# mainboard_v1.net
KiCad netlist of a schematic drawn in Altium Designer
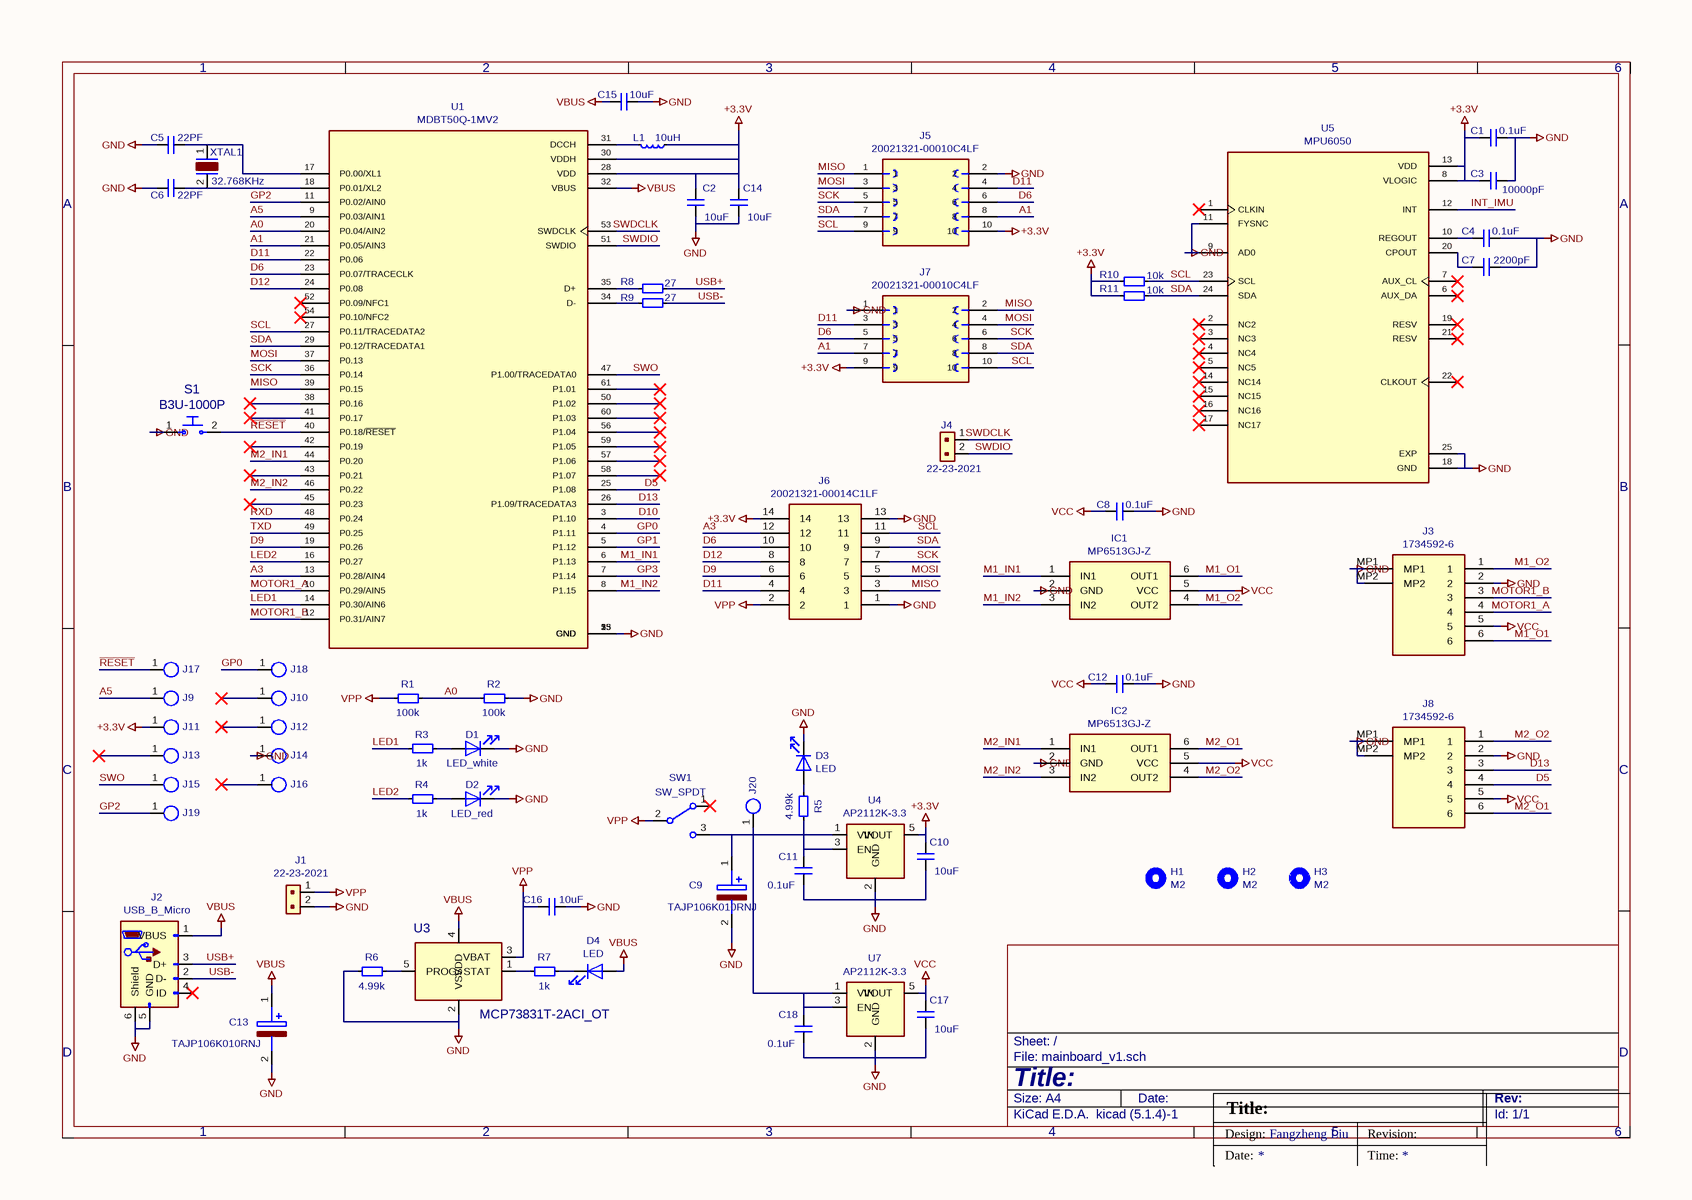
[diagram p0: mainboard_v1.SchDoc]

(export (version "E")
  (design (tool "Eeschema 10.0.6"))
  (components
    (comp (ref "C1") (value "0.1uF") (libsource (lib "Device") (part "C_Small")))
    (comp (ref "C2") (value "10uF") (libsource (lib "Device") (part "C_Small")))
    (comp (ref "C3") (value "10000pF") (libsource (lib "Device") (part "C_Small")))
    (comp (ref "C4") (value "0.1uF") (libsource (lib "Device") (part "C_Small")))
    (comp (ref "C5") (value "22PF") (libsource (lib "Device") (part "C_Small")))
    (comp (ref "C6") (value "22PF") (libsource (lib "Device") (part "C_Small")))
    (comp (ref "C7") (value "2200pF") (libsource (lib "Device") (part "C_Small")))
    (comp (ref "C8") (value "0.1uF") (libsource (lib "Device") (part "C_Small")))
    (comp (ref "C9")
      (value "TAJP106K010RNJ")
      (description "Tantalum Capacitors - Solid SMD 10V 10uF 10%")
      (fields (field (name "MOUSER PART NUMBER") "581-TAJP106K010RNJ"))
      (libsource (lib "SamacSys_Parts") (part "TAJP106K010RNJ"))
    )
    (comp (ref "C10") (value "10uF") (libsource (lib "Device") (part "C_Small")))
    (comp (ref "C11") (value "0.1uF") (libsource (lib "Device") (part "C_Small")))
    (comp (ref "C12") (value "0.1uF") (libsource (lib "Device") (part "C_Small")))
    (comp (ref "C13")
      (value "TAJP106K010RNJ")
      (description "Tantalum Capacitors - Solid SMD 10V 10uF 10%")
      (fields (field (name "MOUSER PART NUMBER") "581-TAJP106K010RNJ"))
      (libsource (lib "SamacSys_Parts") (part "TAJP106K010RNJ"))
    )
    (comp (ref "C14") (value "10uF") (libsource (lib "Device") (part "C_Small")))
    (comp (ref "C15") (value "10uF") (libsource (lib "Device") (part "C_Small")))
    (comp (ref "C16") (value "10uF") (libsource (lib "Device") (part "C_Small")))
    (comp (ref "C17") (value "10uF") (libsource (lib "Device") (part "C_Small")))
    (comp (ref "C18") (value "0.1uF") (libsource (lib "Device") (part "C_Small")))
    (comp (ref "D1") (value "LED_white") (libsource (lib "Device") (part "LED")))
    (comp (ref "D2") (value "LED_red") (libsource (lib "Device") (part "LED")))
    (comp (ref "D3") (value "LED") (libsource (lib "Device") (part "LED")))
    (comp (ref "D4") (value "LED") (libsource (lib "Device") (part "LED")))
    (comp (ref "H1") (value "M2") (libsource (lib "Mechanical") (part "MountingHole")))
    (comp (ref "H2") (value "M2") (libsource (lib "Mechanical") (part "MountingHole")))
    (comp (ref "H3") (value "M2") (libsource (lib "Mechanical") (part "MountingHole")))
    (comp (ref "IC1")
      (value "MP6513GJ-Z")
      (description "Power Switch ICs - Power Distribution 2.5V-21V 0.8A Half Bridge Motor Driver")
      (fields (field (name "MOUSER PART NUMBER") "946-MP6513GJ-Z"))
      (libsource (lib "SamacSys_Parts") (part "MP6513GJ-Z"))
    )
    (comp (ref "IC2")
      (value "MP6513GJ-Z")
      (description "Power Switch ICs - Power Distribution 2.5V-21V 0.8A Half Bridge Motor Driver")
      (fields (field (name "MOUSER PART NUMBER") "946-MP6513GJ-Z"))
      (libsource (lib "SamacSys_Parts") (part "MP6513GJ-Z"))
    )
    (comp (ref "J1")
      (value "22-23-2021")
      (description "CONN HEADER VERT 2POS 2.54MM")
      (fields (field (name "MANUFACTURER") "Molex"))
      (libsource (lib "dk_Rectangular-Connectors-Headers-Male-Pins") (part "22-23-2021"))
    )
    (comp (ref "J2") (value "USB_B_Micro") (libsource (lib "Connector") (part "USB_B_Micro")))
    (comp (ref "J3")
      (value "1734592-6")
      (description "FFC & FPC Connectors FPC CONN. 0.5MM PITCH B/C 6P")
      (fields (field (name "MOUSER PART NUMBER") "571-1734592-6"))
      (libsource (lib "SamacSys_Parts") (part "1734592-6"))
    )
    (comp (ref "J4")
      (value "22-23-2021")
      (description "CONN HEADER VERT 2POS 2.54MM")
      (fields (field (name "MANUFACTURER") "Molex"))
      (libsource (lib "dk_Rectangular-Connectors-Headers-Male-Pins") (part "22-23-2021"))
    )
    (comp (ref "J5")
      (value "20021321-00010C4LF")
      (fields (field (name "MANUFACTURER") "Harwin Inc."))
      (libsource (lib "M50-3100545") (part "M50-3100545"))
    )
    (comp (ref "J6")
      (value "20021321-00014C1LF")
      (description "Headers & Wire Housings 20021321-00014C1LF-RECEPTACLE VT SMT")
      (fields (field (name "MOUSER PART NUMBER") "649-20213210014C1LF"))
      (libsource (lib "SamacSys_Parts") (part "20021321-00014C1LF"))
    )
    (comp (ref "J7")
      (value "20021321-00010C4LF")
      (fields (field (name "MANUFACTURER") "Harwin Inc."))
      (libsource (lib "M50-3100545") (part "M50-3100545"))
    )
    (comp (ref "J8")
      (value "1734592-6")
      (description "FFC & FPC Connectors FPC CONN. 0.5MM PITCH B/C 6P")
      (fields (field (name "MOUSER PART NUMBER") "571-1734592-6"))
      (libsource (lib "SamacSys_Parts") (part "1734592-6"))
    )
    (comp (ref "J9") (value "1_pin_sig") (libsource (lib "Mylib") (part "1_pin_sig")))
    (comp (ref "J10") (value "1_pin_sig") (libsource (lib "Mylib") (part "1_pin_sig")))
    (comp (ref "J11") (value "1_pin_sig") (libsource (lib "Mylib") (part "1_pin_sig")))
    (comp (ref "J12") (value "1_pin_sig") (libsource (lib "Mylib") (part "1_pin_sig")))
    (comp (ref "J13") (value "1_pin_sig") (libsource (lib "Mylib") (part "1_pin_sig")))
    (comp (ref "J14") (value "1_pin_sig") (libsource (lib "Mylib") (part "1_pin_sig")))
    (comp (ref "J15") (value "1_pin_sig") (libsource (lib "Mylib") (part "1_pin_sig")))
    (comp (ref "J16") (value "1_pin_sig") (libsource (lib "Mylib") (part "1_pin_sig")))
    (comp (ref "J17") (value "1_pin_sig") (libsource (lib "Mylib") (part "1_pin_sig")))
    (comp (ref "J18") (value "1_pin_sig") (libsource (lib "Mylib") (part "1_pin_sig")))
    (comp (ref "J19") (value "1_pin_sig") (libsource (lib "Mylib") (part "1_pin_sig")))
    (comp (ref "J20") (value "1_pin_sig") (libsource (lib "Mylib") (part "1_pin_sig")))
    (comp (ref "L1") (value "10uH") (libsource (lib "Device") (part "L_Small")))
    (comp (ref "R1") (value "100k") (libsource (lib "Device") (part "R_Small")))
    (comp (ref "R2") (value "100k") (libsource (lib "Device") (part "R_Small")))
    (comp (ref "R3") (value "1k") (libsource (lib "Device") (part "R_Small")))
    (comp (ref "R4") (value "1k") (libsource (lib "Device") (part "R_Small")))
    (comp (ref "R5") (value "4.99k") (libsource (lib "") (part "R_Small_1")))
    (comp (ref "R6") (value "4.99k") (libsource (lib "Device") (part "R_Small")))
    (comp (ref "R7") (value "1k") (libsource (lib "Device") (part "R_Small")))
    (comp (ref "R8") (value "27") (libsource (lib "Device") (part "R_Small")))
    (comp (ref "R9") (value "27") (libsource (lib "Device") (part "R_Small")))
    (comp (ref "R10") (value "10k") (libsource (lib "Device") (part "R_Small")))
    (comp (ref "R11") (value "10k") (libsource (lib "Device") (part "R_Small")))
    (comp (ref "S1")
      (value "B3U-1000P")
      (description "SWITCH TACTILE SPST-NO 0.05A 12V")
      (fields (field (name "MANUFACTURER") "Omron Electronics Inc-EMC Div"))
      (libsource (lib "dk_Tactile-Switches") (part "B3U-1000P"))
    )
    (comp (ref "SW1") (value "SW_SPDT") (libsource (lib "Switch") (part "SW_SPDT")))
    (comp (ref "U1")
      (value "MDBT50Q-1MV2")
      (fields (field (name "MANUFACTURER") "RAYTAC"))
      (libsource (lib "MDBT50Q-1MV2") (part "MDBT50Q-1MV2"))
    )
    (comp (ref "U3")
      (value "MCP73831T-2ACI_OT")
      (description "IC CONTROLLR LI-ION 4.2V SOT23-5")
      (fields (field (name "MPN") "MCP73831T-2ACI/OT") (field (name "MANUFACTURER") "Microchip Technology"))
      (libsource (lib "dk_PMIC-Battery-Chargers") (part "MCP73831T-2ACI_OT"))
    )
    (comp (ref "U4") (value "AP2112K-3.3") (libsource (lib "Regulator_Linear") (part "AP2112K-3.3")))
    (comp (ref "U5")
      (value "MPU6050")
      (fields (field (name "MANUFACTURER") "TDK InvenSense"))
      (libsource (lib "MPU6050") (part "MPU6050"))
    )
    (comp (ref "U7") (value "AP2112K-3.3") (libsource (lib "Regulator_Linear") (part "AP2112K-3.3")))
    (comp (ref "XTAL1")
      (value "32.768KHz")
      (description "CRYSTAL 32.7680KHZ 12.5PF SMD")
      (fields (field (name "MPN") "ECS-.327-12.5-34B-TR") (field (name "MANUFACTURER") "ECS Inc."))
      (libsource (lib "dk_Crystals") (part "ECS-_327-12_5-34B-TR"))
    )
  )
  (nets
    (net (code "1") (name "+3.3V") (class "Default")
      (node (ref "C1") (pin "2") (pinfunction "2_2") (pintype "passive"))
      (node (ref "C10") (pin "2") (pinfunction "2_2") (pintype "passive"))
      (node (ref "C14") (pin "2") (pinfunction "2_2") (pintype "passive"))
      (node (ref "C2") (pin "2") (pinfunction "2_2") (pintype "passive"))
      (node (ref "C3") (pin "2") (pinfunction "2_2") (pintype "passive"))
      (node (ref "J11") (pin "1") (pinfunction "1_1") (pintype "passive"))
      (node (ref "J5") (pin "10") (pinfunction "10_10") (pintype "passive"))
      (node (ref "J6") (pin "14") (pinfunction "14_14") (pintype "passive"))
      (node (ref "J7") (pin "9") (pinfunction "9_9") (pintype "passive"))
      (node (ref "L1") (pin "1") (pinfunction "1_1") (pintype "passive"))
      (node (ref "R10") (pin "2") (pinfunction "2_2") (pintype "passive"))
      (node (ref "R11") (pin "2") (pinfunction "2_2") (pintype "passive"))
      (node (ref "U1") (pin "28") (pinfunction "VDD_28") (pintype "passive"))
      (node (ref "U1") (pin "30") (pinfunction "VDDH_30") (pintype "passive"))
      (node (ref "U4") (pin "5") (pinfunction "VOUT_5") (pintype "passive"))
      (node (ref "U5") (pin "13") (pinfunction "VDD_13") (pintype "passive"))
      (node (ref "U5") (pin "8") (pinfunction "VLOGIC_8") (pintype "passive"))
    )
    (net (code "2") (name "/A0") (class "Default")
      (node (ref "R1") (pin "1") (pinfunction "1_1") (pintype "passive"))
      (node (ref "R2") (pin "2") (pinfunction "2_2") (pintype "passive"))
      (node (ref "U1") (pin "20") (pinfunction "P0.04/AIN2_20") (pintype "passive"))
    )
    (net (code "3") (name "/A1") (class "Default")
      (node (ref "J5") (pin "8") (pinfunction "8_8") (pintype "passive"))
      (node (ref "J7") (pin "7") (pinfunction "7_7") (pintype "passive"))
      (node (ref "U1") (pin "21") (pinfunction "P0.05/AIN3_21") (pintype "passive"))
    )
    (net (code "4") (name "/A3") (class "Default")
      (node (ref "J6") (pin "12") (pinfunction "12_12") (pintype "passive"))
      (node (ref "U1") (pin "13") (pinfunction "P0.28/AIN4_13") (pintype "passive"))
    )
    (net (code "5") (name "/A5") (class "Default")
      (node (ref "J9") (pin "1") (pinfunction "1_1") (pintype "passive"))
      (node (ref "U1") (pin "9") (pinfunction "P0.03/AIN1_9") (pintype "passive"))
    )
    (net (code "6") (name "/D5") (class "Default")
      (node (ref "J8") (pin "4") (pinfunction "4_4") (pintype "passive"))
      (node (ref "U1") (pin "25") (pinfunction "P1.08_25") (pintype "passive"))
    )
    (net (code "7") (name "/D6") (class "Default")
      (node (ref "J5") (pin "6") (pinfunction "6_6") (pintype "passive"))
      (node (ref "J6") (pin "10") (pinfunction "10_10") (pintype "passive"))
      (node (ref "J7") (pin "5") (pinfunction "5_5") (pintype "passive"))
      (node (ref "U1") (pin "23") (pinfunction "P0.07/TRACECLK_23") (pintype "passive"))
    )
    (net (code "8") (name "/D9") (class "Default")
      (node (ref "J6") (pin "6") (pinfunction "6_6") (pintype "passive"))
      (node (ref "U1") (pin "19") (pinfunction "P0.26_19") (pintype "passive"))
    )
    (net (code "9") (name "/D10") (class "Default")
      (node (ref "U1") (pin "3") (pinfunction "P1.10_3") (pintype "passive"))
    )
    (net (code "10") (name "/D11") (class "Default")
      (node (ref "J5") (pin "4") (pinfunction "4_4") (pintype "passive"))
      (node (ref "J6") (pin "4") (pinfunction "4_4") (pintype "passive"))
      (node (ref "J7") (pin "3") (pinfunction "3_3") (pintype "passive"))
      (node (ref "U1") (pin "22") (pinfunction "P0.06_22") (pintype "passive"))
    )
    (net (code "11") (name "/D12") (class "Default")
      (node (ref "J6") (pin "8") (pinfunction "8_8") (pintype "passive"))
      (node (ref "U1") (pin "24") (pinfunction "P0.08_24") (pintype "passive"))
    )
    (net (code "12") (name "/D13") (class "Default")
      (node (ref "J8") (pin "3") (pinfunction "3_3") (pintype "passive"))
      (node (ref "U1") (pin "26") (pinfunction "P1.09/TRACEDATA3_26") (pintype "passive"))
    )
    (net (code "13") (name "/GP0") (class "Default")
      (node (ref "J18") (pin "1") (pinfunction "1_1") (pintype "passive"))
      (node (ref "U1") (pin "4") (pinfunction "P1.11_4") (pintype "passive"))
    )
    (net (code "14") (name "/GP1") (class "Default")
      (node (ref "U1") (pin "5") (pinfunction "P1.12_5") (pintype "passive"))
    )
    (net (code "15") (name "/GP2") (class "Default")
      (node (ref "J19") (pin "1") (pinfunction "1_1") (pintype "passive"))
      (node (ref "U1") (pin "11") (pinfunction "P0.02/AIN0_11") (pintype "passive"))
    )
    (net (code "16") (name "/GP3") (class "Default")
      (node (ref "U1") (pin "7") (pinfunction "P1.14_7") (pintype "passive"))
    )
    (net (code "17") (name "/INT_IMU") (class "Default")
      (node (ref "U5") (pin "12") (pinfunction "INT_12") (pintype "passive"))
    )
    (net (code "18") (name "/LED1") (class "Default")
      (node (ref "R3") (pin "2") (pinfunction "2_2") (pintype "passive"))
      (node (ref "U1") (pin "14") (pinfunction "P0.30/AIN6_14") (pintype "passive"))
    )
    (net (code "19") (name "/LED2") (class "Default")
      (node (ref "R4") (pin "2") (pinfunction "2_2") (pintype "passive"))
      (node (ref "U1") (pin "16") (pinfunction "P0.27_16") (pintype "passive"))
    )
    (net (code "20") (name "/M1_IN1") (class "Default")
      (node (ref "IC1") (pin "1") (pinfunction "IN1_1") (pintype "passive"))
      (node (ref "U1") (pin "6") (pinfunction "P1.13_6") (pintype "passive"))
    )
    (net (code "21") (name "/M1_IN2") (class "Default")
      (node (ref "IC1") (pin "3") (pinfunction "IN2_3") (pintype "passive"))
      (node (ref "U1") (pin "8") (pinfunction "P1.15_8") (pintype "passive"))
    )
    (net (code "22") (name "/M1_O1") (class "Default")
      (node (ref "IC1") (pin "6") (pinfunction "OUT1_6") (pintype "passive"))
      (node (ref "J3") (pin "6") (pinfunction "6_6") (pintype "passive"))
    )
    (net (code "23") (name "/M1_O2") (class "Default")
      (node (ref "IC1") (pin "4") (pinfunction "OUT2_4") (pintype "passive"))
      (node (ref "J3") (pin "1") (pinfunction "1_1") (pintype "passive"))
    )
    (net (code "24") (name "/M2_IN1") (class "Default")
      (node (ref "IC2") (pin "1") (pinfunction "IN1_1") (pintype "passive"))
      (node (ref "U1") (pin "44") (pinfunction "P0.20_44") (pintype "passive"))
    )
    (net (code "25") (name "/M2_IN2") (class "Default")
      (node (ref "IC2") (pin "3") (pinfunction "IN2_3") (pintype "passive"))
      (node (ref "U1") (pin "46") (pinfunction "P0.22_46") (pintype "passive"))
    )
    (net (code "26") (name "/M2_O1") (class "Default")
      (node (ref "IC2") (pin "6") (pinfunction "OUT1_6") (pintype "passive"))
      (node (ref "J8") (pin "6") (pinfunction "6_6") (pintype "passive"))
    )
    (net (code "27") (name "/M2_O2") (class "Default")
      (node (ref "IC2") (pin "4") (pinfunction "OUT2_4") (pintype "passive"))
      (node (ref "J8") (pin "1") (pinfunction "1_1") (pintype "passive"))
    )
    (net (code "28") (name "/MISO") (class "Default")
      (node (ref "J5") (pin "1") (pinfunction "1_1") (pintype "passive"))
      (node (ref "J6") (pin "3") (pinfunction "3_3") (pintype "passive"))
      (node (ref "J7") (pin "2") (pinfunction "2_2") (pintype "passive"))
      (node (ref "U1") (pin "39") (pinfunction "P0.15_39") (pintype "passive"))
    )
    (net (code "29") (name "/MOSI") (class "Default")
      (node (ref "J5") (pin "3") (pinfunction "3_3") (pintype "passive"))
      (node (ref "J6") (pin "5") (pinfunction "5_5") (pintype "passive"))
      (node (ref "J7") (pin "4") (pinfunction "4_4") (pintype "passive"))
      (node (ref "U1") (pin "37") (pinfunction "P0.13_37") (pintype "passive"))
    )
    (net (code "30") (name "/MOTOR1_A") (class "Default")
      (node (ref "J3") (pin "4") (pinfunction "4_4") (pintype "passive"))
      (node (ref "U1") (pin "10") (pinfunction "P0.29/AIN5_10") (pintype "passive"))
    )
    (net (code "31") (name "/MOTOR1_B") (class "Default")
      (node (ref "J3") (pin "3") (pinfunction "3_3") (pintype "passive"))
      (node (ref "U1") (pin "12") (pinfunction "P0.31/AIN7_12") (pintype "passive"))
    )
    (net (code "32") (name "/RXD") (class "Default")
      (node (ref "U1") (pin "48") (pinfunction "P0.24_48") (pintype "passive"))
    )
    (net (code "33") (name "/SCK") (class "Default")
      (node (ref "J5") (pin "5") (pinfunction "5_5") (pintype "passive"))
      (node (ref "J6") (pin "7") (pinfunction "7_7") (pintype "passive"))
      (node (ref "J7") (pin "6") (pinfunction "6_6") (pintype "passive"))
      (node (ref "U1") (pin "36") (pinfunction "P0.14_36") (pintype "passive"))
    )
    (net (code "34") (name "/SCL") (class "Default")
      (node (ref "J5") (pin "9") (pinfunction "9_9") (pintype "passive"))
      (node (ref "J6") (pin "11") (pinfunction "11_11") (pintype "passive"))
      (node (ref "J7") (pin "10") (pinfunction "10_10") (pintype "passive"))
      (node (ref "R10") (pin "1") (pinfunction "1_1") (pintype "passive"))
      (node (ref "U1") (pin "27") (pinfunction "P0.11/TRACEDATA2_27") (pintype "passive"))
      (node (ref "U5") (pin "23") (pinfunction "SCL_23") (pintype "passive"))
    )
    (net (code "35") (name "/SDA") (class "Default")
      (node (ref "J5") (pin "7") (pinfunction "7_7") (pintype "passive"))
      (node (ref "J6") (pin "9") (pinfunction "9_9") (pintype "passive"))
      (node (ref "J7") (pin "8") (pinfunction "8_8") (pintype "passive"))
      (node (ref "R11") (pin "1") (pinfunction "1_1") (pintype "passive"))
      (node (ref "U1") (pin "29") (pinfunction "P0.12/TRACEDATA1_29") (pintype "passive"))
      (node (ref "U5") (pin "24") (pinfunction "SDA_24") (pintype "passive"))
    )
    (net (code "36") (name "/SWDCLK") (class "Default")
      (node (ref "J4") (pin "1") (pinfunction "1_1") (pintype "passive"))
      (node (ref "U1") (pin "53") (pinfunction "SWDCLK_53") (pintype "passive"))
    )
    (net (code "37") (name "/SWDIO") (class "Default")
      (node (ref "J4") (pin "2") (pinfunction "2_2") (pintype "passive"))
      (node (ref "U1") (pin "51") (pinfunction "SWDIO_51") (pintype "passive"))
    )
    (net (code "38") (name "/SWO") (class "Default")
      (node (ref "J15") (pin "1") (pinfunction "1_1") (pintype "passive"))
      (node (ref "U1") (pin "47") (pinfunction "P1.00/TRACEDATA0_47") (pintype "passive"))
    )
    (net (code "39") (name "/TXD") (class "Default")
      (node (ref "U1") (pin "49") (pinfunction "P0.25_49") (pintype "passive"))
    )
    (net (code "40") (name "/USB+") (class "Default")
      (node (ref "J2") (pin "3") (pinfunction "D+_3") (pintype "passive"))
      (node (ref "R8") (pin "1") (pinfunction "1_1") (pintype "passive"))
    )
    (net (code "41") (name "/USB-") (class "Default")
      (node (ref "J2") (pin "2") (pinfunction "D-_2") (pintype "passive"))
      (node (ref "R9") (pin "1") (pinfunction "1_1") (pintype "passive"))
    )
    (net (code "42") (name "/~{RESET}") (class "Default")
      (node (ref "J17") (pin "1") (pinfunction "1_1") (pintype "passive"))
      (node (ref "S1") (pin "2") (pinfunction "2_2") (pintype "passive"))
      (node (ref "U1") (pin "40") (pinfunction "P0.18/~{RESET}_40") (pintype "passive"))
    )
    (net (code "43") (name "GND") (class "Default")
      (node (ref "C1") (pin "1") (pinfunction "1_1") (pintype "passive"))
      (node (ref "C10") (pin "1") (pinfunction "1_1") (pintype "passive"))
      (node (ref "C11") (pin "1") (pinfunction "1_1") (pintype "passive"))
      (node (ref "C12") (pin "1") (pinfunction "1_1") (pintype "passive"))
      (node (ref "C13") (pin "2") (pinfunction "2_2") (pintype "passive"))
      (node (ref "C14") (pin "1") (pinfunction "1_1") (pintype "passive"))
      (node (ref "C15") (pin "1") (pinfunction "1_1") (pintype "passive"))
      (node (ref "C16") (pin "1") (pinfunction "1_1") (pintype "passive"))
      (node (ref "C17") (pin "1") (pinfunction "1_1") (pintype "passive"))
      (node (ref "C18") (pin "1") (pinfunction "1_1") (pintype "passive"))
      (node (ref "C2") (pin "1") (pinfunction "1_1") (pintype "passive"))
      (node (ref "C3") (pin "1") (pinfunction "1_1") (pintype "passive"))
      (node (ref "C4") (pin "1") (pinfunction "1_1") (pintype "passive"))
      (node (ref "C5") (pin "2") (pinfunction "2_2") (pintype "passive"))
      (node (ref "C6") (pin "2") (pinfunction "2_2") (pintype "passive"))
      (node (ref "C7") (pin "1") (pinfunction "1_1") (pintype "passive"))
      (node (ref "C8") (pin "1") (pinfunction "1_1") (pintype "passive"))
      (node (ref "C9") (pin "2") (pinfunction "2_2") (pintype "passive"))
      (node (ref "D1") (pin "1") (pinfunction "K_1") (pintype "passive"))
      (node (ref "D2") (pin "1") (pinfunction "K_1") (pintype "passive"))
      (node (ref "D3") (pin "1") (pinfunction "K_1") (pintype "passive"))
      (node (ref "IC1") (pin "2") (pinfunction "GND_2") (pintype "passive"))
      (node (ref "IC2") (pin "2") (pinfunction "GND_2") (pintype "passive"))
      (node (ref "J1") (pin "2") (pinfunction "2_2") (pintype "passive"))
      (node (ref "J14") (pin "1") (pinfunction "1_1") (pintype "passive"))
      (node (ref "J2") (pin "5") (pinfunction "GND_5") (pintype "passive"))
      (node (ref "J2") (pin "6") (pinfunction "Shield_6") (pintype "passive"))
      (node (ref "J3") (pin "2") (pinfunction "2_2") (pintype "passive"))
      (node (ref "J3") (pin "MP1") (pinfunction "MP1_MP1") (pintype "passive"))
      (node (ref "J3") (pin "MP2") (pinfunction "MP2_MP2") (pintype "passive"))
      (node (ref "J5") (pin "2") (pinfunction "2_2") (pintype "passive"))
      (node (ref "J6") (pin "1") (pinfunction "1_1") (pintype "passive"))
      (node (ref "J6") (pin "13") (pinfunction "13_13") (pintype "passive"))
      (node (ref "J7") (pin "1") (pinfunction "1_1") (pintype "passive"))
      (node (ref "J8") (pin "2") (pinfunction "2_2") (pintype "passive"))
      (node (ref "J8") (pin "MP1") (pinfunction "MP1_MP1") (pintype "passive"))
      (node (ref "J8") (pin "MP2") (pinfunction "MP2_MP2") (pintype "passive"))
      (node (ref "R2") (pin "1") (pinfunction "1_1") (pintype "passive"))
      (node (ref "R6") (pin "2") (pinfunction "2_2") (pintype "passive"))
      (node (ref "S1") (pin "1") (pinfunction "1_1") (pintype "passive"))
      (node (ref "U1") (pin "1") (pinfunction "GND_1") (pintype "passive"))
      (node (ref "U1") (pin "15") (pinfunction "GND_15") (pintype "passive"))
      (node (ref "U1") (pin "2") (pinfunction "GND_2") (pintype "passive"))
      (node (ref "U1") (pin "33") (pinfunction "GND_33") (pintype "passive"))
      (node (ref "U1") (pin "55") (pinfunction "GND_55") (pintype "passive"))
      (node (ref "U3") (pin "2") (pinfunction "VSS_2") (pintype "passive"))
      (node (ref "U4") (pin "2") (pinfunction "GND_2") (pintype "passive"))
      (node (ref "U5") (pin "11") (pinfunction "FYSNC_11") (pintype "passive"))
      (node (ref "U5") (pin "18") (pinfunction "GND_18") (pintype "passive"))
      (node (ref "U5") (pin "25") (pinfunction "EXP_25") (pintype "passive"))
      (node (ref "U5") (pin "9") (pinfunction "AD0_9") (pintype "passive"))
      (node (ref "U7") (pin "2") (pinfunction "GND_2") (pintype "passive"))
    )
    (net (code "44") (name "Net-(D1-A)") (class "Default")
      (node (ref "D1") (pin "2") (pinfunction "A_2") (pintype "passive"))
      (node (ref "R3") (pin "1") (pinfunction "1_1") (pintype "passive"))
    )
    (net (code "45") (name "Net-(D2-A)") (class "Default")
      (node (ref "D2") (pin "2") (pinfunction "A_2") (pintype "passive"))
      (node (ref "R4") (pin "1") (pinfunction "1_1") (pintype "passive"))
    )
    (net (code "46") (name "Net-(D3-A)") (class "Default")
      (node (ref "D3") (pin "2") (pinfunction "A_2") (pintype "passive"))
      (node (ref "R5") (pin "2") (pinfunction "2_2") (pintype "passive"))
    )
    (net (code "47") (name "Net-(D4-K)") (class "Default")
      (node (ref "D4") (pin "1") (pinfunction "K_1") (pintype "passive"))
      (node (ref "R7") (pin "1") (pinfunction "1_1") (pintype "passive"))
    )
    (net (code "48") (name "Net-(SW1-C)") (class "Default")
      (node (ref "C11") (pin "2") (pinfunction "2_2") (pintype "passive"))
      (node (ref "C18") (pin "2") (pinfunction "2_2") (pintype "passive"))
      (node (ref "C9") (pin "1") (pinfunction "1_1") (pintype "passive"))
      (node (ref "J20") (pin "1") (pinfunction "1_1") (pintype "passive"))
      (node (ref "R5") (pin "1") (pinfunction "1_1") (pintype "passive"))
      (node (ref "SW1") (pin "3") (pinfunction "C_3") (pintype "passive"))
      (node (ref "U4") (pin "1") (pinfunction "VIN_1") (pintype "passive"))
      (node (ref "U4") (pin "3") (pinfunction "EN_3") (pintype "passive"))
      (node (ref "U7") (pin "1") (pinfunction "VIN_1") (pintype "passive"))
      (node (ref "U7") (pin "3") (pinfunction "EN_3") (pintype "passive"))
    )
    (net (code "49") (name "Net-(U1-D+)") (class "Default")
      (node (ref "R8") (pin "2") (pinfunction "2_2") (pintype "passive"))
      (node (ref "U1") (pin "35") (pinfunction "D+_35") (pintype "passive"))
    )
    (net (code "50") (name "Net-(U1-D-)") (class "Default")
      (node (ref "R9") (pin "2") (pinfunction "2_2") (pintype "passive"))
      (node (ref "U1") (pin "34") (pinfunction "D-_34") (pintype "passive"))
    )
    (net (code "51") (name "Net-(U1-DCCH)") (class "Default")
      (node (ref "L1") (pin "2") (pinfunction "2_2") (pintype "passive"))
      (node (ref "U1") (pin "31") (pinfunction "DCCH_31") (pintype "passive"))
    )
    (net (code "52") (name "Net-(U1-P0.00{slash}XL1)") (class "Default")
      (node (ref "C5") (pin "1") (pinfunction "1_1") (pintype "passive"))
      (node (ref "U1") (pin "17") (pinfunction "P0.00/XL1_17") (pintype "passive"))
      (node (ref "XTAL1") (pin "1") (pinfunction "1_1") (pintype "passive"))
    )
    (net (code "53") (name "Net-(U1-P0.01{slash}XL2)") (class "Default")
      (node (ref "C6") (pin "1") (pinfunction "1_1") (pintype "passive"))
      (node (ref "U1") (pin "18") (pinfunction "P0.01/XL2_18") (pintype "passive"))
      (node (ref "XTAL1") (pin "2") (pinfunction "2_2") (pintype "passive"))
    )
    (net (code "54") (name "Net-(U3-PROG)") (class "Default")
      (node (ref "R6") (pin "1") (pinfunction "1_1") (pintype "passive"))
      (node (ref "U3") (pin "5") (pinfunction "PROG_5") (pintype "passive"))
    )
    (net (code "55") (name "Net-(U3-STAT)") (class "Default")
      (node (ref "R7") (pin "2") (pinfunction "2_2") (pintype "passive"))
      (node (ref "U3") (pin "1") (pinfunction "STAT_1") (pintype "passive"))
    )
    (net (code "56") (name "Net-(U5-CPOUT)") (class "Default")
      (node (ref "C7") (pin "2") (pinfunction "2_2") (pintype "passive"))
      (node (ref "U5") (pin "20") (pinfunction "CPOUT_20") (pintype "passive"))
    )
    (net (code "57") (name "Net-(U5-REGOUT)") (class "Default")
      (node (ref "C4") (pin "2") (pinfunction "2_2") (pintype "passive"))
      (node (ref "U5") (pin "10") (pinfunction "REGOUT_10") (pintype "passive"))
    )
    (net (code "58") (name "VBUS") (class "Default")
      (node (ref "C13") (pin "1") (pinfunction "1_1") (pintype "passive"))
      (node (ref "C15") (pin "2") (pinfunction "2_2") (pintype "passive"))
      (node (ref "D4") (pin "2") (pinfunction "A_2") (pintype "passive"))
      (node (ref "J2") (pin "1") (pinfunction "VBUS_1") (pintype "passive"))
      (node (ref "U1") (pin "32") (pinfunction "VBUS_32") (pintype "passive"))
      (node (ref "U3") (pin "4") (pinfunction "VDD_4") (pintype "passive"))
    )
    (net (code "59") (name "VCC") (class "Default")
      (node (ref "C12") (pin "2") (pinfunction "2_2") (pintype "passive"))
      (node (ref "C17") (pin "2") (pinfunction "2_2") (pintype "passive"))
      (node (ref "C8") (pin "2") (pinfunction "2_2") (pintype "passive"))
      (node (ref "IC1") (pin "5") (pinfunction "VCC_5") (pintype "passive"))
      (node (ref "IC2") (pin "5") (pinfunction "VCC_5") (pintype "passive"))
      (node (ref "J3") (pin "5") (pinfunction "5_5") (pintype "passive"))
      (node (ref "J8") (pin "5") (pinfunction "5_5") (pintype "passive"))
      (node (ref "U7") (pin "5") (pinfunction "VOUT_5") (pintype "passive"))
    )
    (net (code "60") (name "VPP") (class "Default")
      (node (ref "C16") (pin "2") (pinfunction "2_2") (pintype "passive"))
      (node (ref "J1") (pin "1") (pinfunction "1_1") (pintype "passive"))
      (node (ref "J6") (pin "2") (pinfunction "2_2") (pintype "passive"))
      (node (ref "R1") (pin "2") (pinfunction "2_2") (pintype "passive"))
      (node (ref "SW1") (pin "2") (pinfunction "B_2") (pintype "passive"))
      (node (ref "U3") (pin "3") (pinfunction "VBAT_3") (pintype "passive"))
    )
    (net (code "61") (name "unconnected-(J2-ID-Pad4)") (class "Default")
      (node (ref "J2") (pin "4") (pinfunction "ID_4") (pintype "passive+no_connect"))
    )
    (net (code "62") (name "unconnected-(J10-Pad1)") (class "Default")
      (node (ref "J10") (pin "1") (pinfunction "1_1") (pintype "passive+no_connect"))
    )
    (net (code "63") (name "unconnected-(J12-Pad1)") (class "Default")
      (node (ref "J12") (pin "1") (pinfunction "1_1") (pintype "passive+no_connect"))
    )
    (net (code "64") (name "unconnected-(J13-Pad1)") (class "Default")
      (node (ref "J13") (pin "1") (pinfunction "1_1") (pintype "passive+no_connect"))
    )
    (net (code "65") (name "unconnected-(J16-Pad1)") (class "Default")
      (node (ref "J16") (pin "1") (pinfunction "1_1") (pintype "passive+no_connect"))
    )
    (net (code "66") (name "unconnected-(SW1-A-Pad1)") (class "Default")
      (node (ref "SW1") (pin "1") (pinfunction "A_1") (pintype "passive+no_connect"))
    )
    (net (code "67") (name "unconnected-(U1-P0.09{slash}NFC1-Pad52)") (class "Default")
      (node (ref "U1") (pin "52") (pinfunction "P0.09/NFC1_52") (pintype "passive+no_connect"))
    )
    (net (code "68") (name "unconnected-(U1-P0.10{slash}NFC2-Pad54)") (class "Default")
      (node (ref "U1") (pin "54") (pinfunction "P0.10/NFC2_54") (pintype "passive+no_connect"))
    )
    (net (code "69") (name "unconnected-(U1-P0.16-Pad38)") (class "Default")
      (node (ref "U1") (pin "38") (pinfunction "P0.16_38") (pintype "passive+no_connect"))
    )
    (net (code "70") (name "unconnected-(U1-P0.17-Pad41)") (class "Default")
      (node (ref "U1") (pin "41") (pinfunction "P0.17_41") (pintype "passive+no_connect"))
    )
    (net (code "71") (name "unconnected-(U1-P0.19-Pad42)") (class "Default")
      (node (ref "U1") (pin "42") (pinfunction "P0.19_42") (pintype "passive+no_connect"))
    )
    (net (code "72") (name "unconnected-(U1-P0.21-Pad43)") (class "Default")
      (node (ref "U1") (pin "43") (pinfunction "P0.21_43") (pintype "passive+no_connect"))
    )
    (net (code "73") (name "unconnected-(U1-P0.23-Pad45)") (class "Default")
      (node (ref "U1") (pin "45") (pinfunction "P0.23_45") (pintype "passive+no_connect"))
    )
    (net (code "74") (name "unconnected-(U1-P1.01-Pad61)") (class "Default")
      (node (ref "U1") (pin "61") (pinfunction "P1.01_61") (pintype "passive+no_connect"))
    )
    (net (code "75") (name "unconnected-(U1-P1.02-Pad50)") (class "Default")
      (node (ref "U1") (pin "50") (pinfunction "P1.02_50") (pintype "passive+no_connect"))
    )
    (net (code "76") (name "unconnected-(U1-P1.03-Pad60)") (class "Default")
      (node (ref "U1") (pin "60") (pinfunction "P1.03_60") (pintype "passive+no_connect"))
    )
    (net (code "77") (name "unconnected-(U1-P1.04-Pad56)") (class "Default")
      (node (ref "U1") (pin "56") (pinfunction "P1.04_56") (pintype "passive+no_connect"))
    )
    (net (code "78") (name "unconnected-(U1-P1.05-Pad59)") (class "Default")
      (node (ref "U1") (pin "59") (pinfunction "P1.05_59") (pintype "passive+no_connect"))
    )
    (net (code "79") (name "unconnected-(U1-P1.06-Pad57)") (class "Default")
      (node (ref "U1") (pin "57") (pinfunction "P1.06_57") (pintype "passive+no_connect"))
    )
    (net (code "80") (name "unconnected-(U1-P1.07-Pad58)") (class "Default")
      (node (ref "U1") (pin "58") (pinfunction "P1.07_58") (pintype "passive+no_connect"))
    )
    (net (code "81") (name "unconnected-(U4-NC-Pad4)") (class "Default")
      (node (ref "U4") (pin "4") (pinfunction "NC_4") (pintype "passive"))
    )
    (net (code "82") (name "unconnected-(U5-AUX_CL-Pad7)") (class "Default")
      (node (ref "U5") (pin "7") (pinfunction "AUX_CL_7") (pintype "passive+no_connect"))
    )
    (net (code "83") (name "unconnected-(U5-AUX_DA-Pad6)") (class "Default")
      (node (ref "U5") (pin "6") (pinfunction "AUX_DA_6") (pintype "passive+no_connect"))
    )
    (net (code "84") (name "unconnected-(U5-CLKIN-Pad1)") (class "Default")
      (node (ref "U5") (pin "1") (pinfunction "CLKIN_1") (pintype "passive+no_connect"))
    )
    (net (code "85") (name "unconnected-(U5-CLKOUT-Pad22)") (class "Default")
      (node (ref "U5") (pin "22") (pinfunction "CLKOUT_22") (pintype "passive+no_connect"))
    )
    (net (code "86") (name "unconnected-(U5-NC2-Pad2)") (class "Default")
      (node (ref "U5") (pin "2") (pinfunction "NC2_2") (pintype "passive+no_connect"))
    )
    (net (code "87") (name "unconnected-(U5-NC3-Pad3)") (class "Default")
      (node (ref "U5") (pin "3") (pinfunction "NC3_3") (pintype "passive+no_connect"))
    )
    (net (code "88") (name "unconnected-(U5-NC4-Pad4)") (class "Default")
      (node (ref "U5") (pin "4") (pinfunction "NC4_4") (pintype "passive+no_connect"))
    )
    (net (code "89") (name "unconnected-(U5-NC5-Pad5)") (class "Default")
      (node (ref "U5") (pin "5") (pinfunction "NC5_5") (pintype "passive+no_connect"))
    )
    (net (code "90") (name "unconnected-(U5-NC14-Pad14)") (class "Default")
      (node (ref "U5") (pin "14") (pinfunction "NC14_14") (pintype "passive+no_connect"))
    )
    (net (code "91") (name "unconnected-(U5-NC15-Pad15)") (class "Default")
      (node (ref "U5") (pin "15") (pinfunction "NC15_15") (pintype "passive+no_connect"))
    )
    (net (code "92") (name "unconnected-(U5-NC16-Pad16)") (class "Default")
      (node (ref "U5") (pin "16") (pinfunction "NC16_16") (pintype "passive+no_connect"))
    )
    (net (code "93") (name "unconnected-(U5-NC17-Pad17)") (class "Default")
      (node (ref "U5") (pin "17") (pinfunction "NC17_17") (pintype "passive+no_connect"))
    )
    (net (code "94") (name "unconnected-(U5-RESV-Pad19)") (class "Default")
      (node (ref "U5") (pin "19") (pinfunction "RESV_19") (pintype "passive+no_connect"))
    )
    (net (code "95") (name "unconnected-(U5-RESV-Pad21)") (class "Default")
      (node (ref "U5") (pin "21") (pinfunction "RESV_21") (pintype "passive+no_connect"))
    )
    (net (code "96") (name "unconnected-(U7-NC-Pad4)") (class "Default")
      (node (ref "U7") (pin "4") (pinfunction "NC_4") (pintype "passive"))
    )
  )
)
